# ATtiny_Connections.net
KiCad netlist of a schematic drawn in Altium Designer
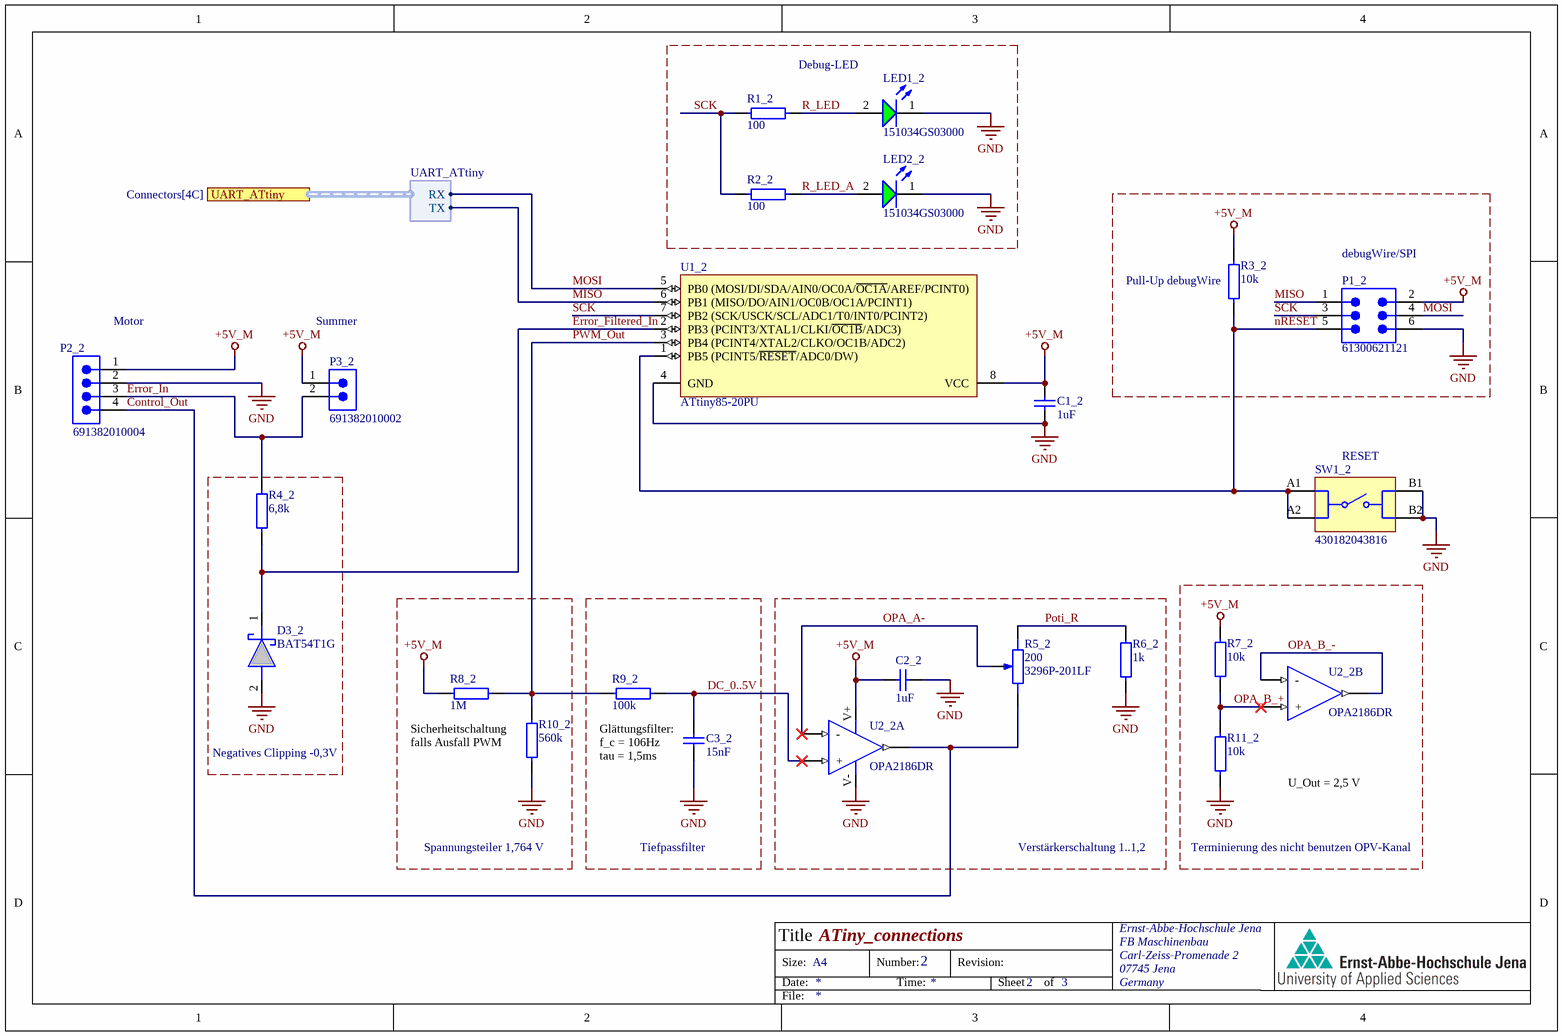
[diagram p0: ATtiny_Connections.SchDoc]

(export (version "E")
  (design (tool "Eeschema 10.0.6"))
  (components
    (comp (ref "C1_2")
      (value "1uF")
      (footprint "SMD-0805")
      (description "Kondensator")
      (libsource (lib "SMD") (part "C"))
    )
    (comp (ref "C2_2")
      (value "1uF")
      (footprint "SMD-0805")
      (description "Kondensator")
      (libsource (lib "SMD") (part "C"))
    )
    (comp (ref "C3_2")
      (value "15nF")
      (footprint "SMD-0805")
      (description "Kondensator")
      (libsource (lib "SMD") (part "C"))
    )
    (comp (ref "D3_2")
      (value "BAT54T1G")
      (footprint "SOD3716X135N")
      (fields (field (name "MOUSER PART NUMBER") "863-BAT54T1G"))
      (libsource (lib "BAT54T1G") (part "BAT54T1G"))
    )
    (comp (ref "LED1_2")
      (value "Green, 3.2V, 30°")
      (footprint "WL-TMRW_D3.9H5.3")
      (description "WL-TMRW Mono-color Round Waterclear, THT, D3.9 x H5.3mm, Green, 3.2V, 30°")
      (fields
        (field (name "MANUFACTURER PART NUMBER") "151034GS03000")
        (field (name "MANUFACTURER") "Wurth Elektronik")
      )
      (libsource (lib "WL-TMRW (rev22b)") (part "151034GS03000"))
    )
    (comp (ref "LED2_2")
      (value "Green, 3.2V, 30°")
      (footprint "WL-TMRW_D3.9H5.3")
      (description "WL-TMRW Mono-color Round Waterclear, THT, D3.9 x H5.3mm, Green, 3.2V, 30°")
      (fields
        (field (name "MANUFACTURER PART NUMBER") "151034GS03000")
        (field (name "MANUFACTURER") "Wurth Elektronik")
      )
      (libsource (lib "WL-TMRW (rev22b)") (part "151034GS03000"))
    )
    (comp (ref "P1_2")
      (value "61300621121")
      (footprint "61300621121")
      (description "WR-PHD Pin Header, THT, Vertical, pitch 2.54mm, 2 Row, 6P")
      (fields
        (field (name "MANUFACTURER PART NUMBER") "61300621121")
        (field (name "MANUFACTURER") "Wurth Elektronik")
      )
      (libsource (lib "Altium_WR-PHD (rev24a)") (part "61300621121"))
    )
    (comp (ref "P2_2")
      (value "691382010004")
      (footprint "691382010004")
      (description "WR-TBL Series 382 Horizontal PCB Header, THT, pitch 2.5mm, 04p")
      (fields (field (name "MANUFACTURER") "Wurth Elektronik"))
      (libsource (lib "Altium_WR-TBL_Pluggable Connector (rev25d)") (part "691382010004"))
    )
    (comp (ref "P3_2")
      (value "691382010002")
      (footprint "691382010002")
      (description "WR-TBL Series 382 Horizontal PCB Header, THT, pitch 2.5mm, 02p")
      (fields (field (name "MANUFACTURER") "Wurth Elektronik"))
      (libsource (lib "Altium_WR-TBL_Pluggable Connector (rev25d)") (part "691382010002"))
    )
    (comp (ref "R1_2")
      (value "100")
      (footprint "R-SMD-0805")
      (description "Widerstand")
      (libsource (lib "SMD") (part "R"))
    )
    (comp (ref "R2_2")
      (value "100")
      (footprint "R-SMD-0805")
      (description "Widerstand")
      (libsource (lib "SMD") (part "R"))
    )
    (comp (ref "R3_2")
      (value "10k")
      (footprint "R-SMD-0805")
      (description "Widerstand")
      (libsource (lib "SMD") (part "R"))
    )
    (comp (ref "R4_2")
      (value "6,8k")
      (footprint "R-SMD-0805")
      (description "Widerstand")
      (libsource (lib "SMD") (part "R"))
    )
    (comp (ref "R5_2")
      (value "200")
      (footprint "3296P-1-201LF")
      (fields
        (field (name "PARTNUMBER") "PV36P???C01B00")
        (field (name "MANUFACTURER PART NR.") "3296P-201LF")
      )
      (libsource (lib "TrimmPotentiometer") (part "3296P-1-201LF"))
    )
    (comp (ref "R6_2")
      (value "1k")
      (footprint "R-SMD-0805")
      (description "Widerstand")
      (libsource (lib "SMD") (part "R"))
    )
    (comp (ref "R7_2")
      (value "10k")
      (footprint "R-SMD-0805")
      (description "Widerstand")
      (libsource (lib "SMD") (part "R"))
    )
    (comp (ref "R8_2")
      (value "1M")
      (footprint "R-SMD-0805")
      (description "Widerstand")
      (libsource (lib "SMD") (part "R"))
    )
    (comp (ref "R9_2")
      (value "100k")
      (footprint "R-SMD-0805")
      (description "Widerstand")
      (libsource (lib "SMD") (part "R"))
    )
    (comp (ref "R10_2")
      (value "560k")
      (footprint "R-SMD-0805")
      (description "Widerstand")
      (libsource (lib "SMD") (part "R"))
    )
    (comp (ref "R11_2")
      (value "10k")
      (footprint "R-SMD-0805")
      (description "Widerstand")
      (libsource (lib "SMD") (part "R"))
    )
    (comp (ref "SW1_2")
      (value "430182043816")
      (footprint "430182043816")
      (description "WS-TASV SMT Tact Switch, 6mm x 6mm, 160gf, SPST-NO, 12V, 50mA")
      (fields (field (name "MANUFACTURER") "Wurth Elektronik"))
      (libsource (lib "Altium_WS-TASV (rev24d)") (part "430182043816"))
    )
    (comp (ref "U1_2")
      (value "ATtiny85-20PU")
      (footprint "8P3")
      (libsource (lib "Atmel Microcontroller tinyAVR") (part "ATtiny85-20PU"))
    )
    (comp (ref "U2_2")
      (value "OPA2186DR")
      (footprint "SOIC127P600-8BM")
      (libsource (lib "TI-OPV-BB") (part "OPA2186"))
    )
  )
  (nets
    (net (code "2") (name "+5V_M") (class "Default")
      (node (ref "C1_2") (pin "2") (pinfunction "2_2") (pintype "passive"))
      (node (ref "C2_2") (pin "2") (pinfunction "2_2") (pintype "passive"))
      (node (ref "P1_2") (pin "2") (pinfunction "2_2") (pintype "passive"))
      (node (ref "P2_2") (pin "1") (pinfunction "1_1") (pintype "passive"))
      (node (ref "P3_2") (pin "1") (pinfunction "1_1") (pintype "passive"))
      (node (ref "R3_2") (pin "2") (pinfunction "2_2") (pintype "passive"))
      (node (ref "R7_2") (pin "2") (pinfunction "2_2") (pintype "passive"))
      (node (ref "R8_2") (pin "1") (pinfunction "1_1") (pintype "passive"))
      (node (ref "U1_2") (pin "8") (pinfunction "VCC_8") (pintype "power_in"))
      (node (ref "U2_2") (pin "V+") (pinfunction "V+_V+") (pintype "power_in"))
    )
    (net (code "3") (name "/Control_Out") (class "Default")
      (node (ref "P2_2") (pin "4") (pinfunction "4_4") (pintype "passive"))
      (node (ref "R5_2") (pin "1") (pinfunction "1_1") (pintype "passive"))
      (node (ref "U2_2") (pin "OUTA") (pinfunction "OUT_OUTA") (pintype "output"))
    )
    (net (code "4") (name "/DC_0..5V") (class "Default")
      (node (ref "C3_2") (pin "2") (pinfunction "2_2") (pintype "passive"))
      (node (ref "R9_2") (pin "2") (pinfunction "2_2") (pintype "passive"))
      (node (ref "U2_2") (pin "IPA") (pinfunction "+_IPA") (pintype "input"))
    )
    (net (code "5") (name "/Error_Filtered_In") (class "Default")
      (node (ref "D3_2") (pin "1") (pinfunction "K_1") (pintype "passive"))
      (node (ref "R4_2") (pin "1") (pinfunction "1_1") (pintype "passive"))
      (node (ref "U1_2") (pin "2") (pinfunction "PB3_(PCINT3/XTAL1/CLKI/~{OC1B}/ADC3)_2") (pintype "bidirectional"))
    )
    (net (code "6") (name "/Error_In") (class "Default")
      (node (ref "P2_2") (pin "3") (pinfunction "3_3") (pintype "passive"))
      (node (ref "P3_2") (pin "2") (pinfunction "2_2") (pintype "passive"))
      (node (ref "R4_2") (pin "2") (pinfunction "2_2") (pintype "passive"))
    )
    (net (code "7") (name "/MISO") (class "Default")
      (node (ref "P1_2") (pin "1") (pinfunction "1_1") (pintype "passive"))
      (node (ref "U1_2") (pin "6") (pinfunction "PB1_(MISO/DO/AIN1/OC0B/OC1A/PCINT1)_6") (pintype "bidirectional"))
    )
    (net (code "8") (name "/MOSI") (class "Default")
      (node (ref "P1_2") (pin "4") (pinfunction "4_4") (pintype "passive"))
      (node (ref "U1_2") (pin "5") (pinfunction "PB0_(MOSI/DI/SDA/AIN0/OC0A/~{OC1A}/AREF/PCINT0)_5") (pintype "bidirectional"))
    )
    (net (code "9") (name "/OPA_A-") (class "Default")
      (node (ref "R5_2") (pin "2") (pinfunction "TAP_2") (pintype "passive"))
      (node (ref "U2_2") (pin "INA") (pinfunction "-_INA") (pintype "input"))
    )
    (net (code "10") (name "/OPA_B_+") (class "Default")
      (node (ref "R11_2") (pin "2") (pinfunction "2_2") (pintype "passive"))
      (node (ref "R7_2") (pin "1") (pinfunction "1_1") (pintype "passive"))
      (node (ref "U2_2") (pin "IPB") (pinfunction "+_IPB") (pintype "input"))
    )
    (net (code "11") (name "/OPA_B_-") (class "Default")
      (node (ref "U2_2") (pin "INB") (pinfunction "-_INB") (pintype "input"))
      (node (ref "U2_2") (pin "OUTB") (pinfunction "OUT_OUTB") (pintype "output"))
    )
    (net (code "12") (name "/PWM_Out") (class "Default")
      (node (ref "R10_2") (pin "2") (pinfunction "2_2") (pintype "passive"))
      (node (ref "R8_2") (pin "2") (pinfunction "2_2") (pintype "passive"))
      (node (ref "R9_2") (pin "1") (pinfunction "1_1") (pintype "passive"))
      (node (ref "U1_2") (pin "3") (pinfunction "PB4_(PCINT4/XTAL2/CLKO/OC1B/ADC2)_3") (pintype "bidirectional"))
    )
    (net (code "13") (name "/Poti_R") (class "Default")
      (node (ref "R5_2") (pin "3") (pinfunction "3_3") (pintype "passive"))
      (node (ref "R6_2") (pin "1") (pinfunction "1_1") (pintype "passive"))
    )
    (net (code "14") (name "/R_LED") (class "Default")
      (node (ref "LED1_2") (pin "2") (pinfunction "A_2") (pintype "passive"))
      (node (ref "R1_2") (pin "2") (pinfunction "2_2") (pintype "passive"))
    )
    (net (code "15") (name "/R_LED_A") (class "Default")
      (node (ref "LED2_2") (pin "2") (pinfunction "A_2") (pintype "passive"))
      (node (ref "R2_2") (pin "2") (pinfunction "2_2") (pintype "passive"))
    )
    (net (code "16") (name "/SCK") (class "Default")
      (node (ref "P1_2") (pin "3") (pinfunction "3_3") (pintype "passive"))
      (node (ref "R1_2") (pin "1") (pinfunction "1_1") (pintype "passive"))
      (node (ref "R2_2") (pin "1") (pinfunction "1_1") (pintype "passive"))
      (node (ref "U1_2") (pin "7") (pinfunction "PB2_(SCK/USCK/SCL/ADC1/T0/INT0/PCINT2)_7") (pintype "bidirectional"))
    )
    (net (code "17") (name "/nRESET") (class "Default")
      (node (ref "P1_2") (pin "5") (pinfunction "5_5") (pintype "passive"))
      (node (ref "R3_2") (pin "1") (pinfunction "1_1") (pintype "passive"))
      (node (ref "SW1_2") (pin "A1") (pinfunction "A1_A1") (pintype "passive"))
      (node (ref "SW1_2") (pin "A2") (pinfunction "A2_A2") (pintype "passive"))
      (node (ref "U1_2") (pin "1") (pinfunction "PB5_(PCINT5/~{RESET}/ADC0/DW)_1") (pintype "bidirectional"))
    )
    (net (code "19") (name "GND") (class "Default")
      (node (ref "C1_2") (pin "1") (pinfunction "1_1") (pintype "passive"))
      (node (ref "C2_2") (pin "1") (pinfunction "1_1") (pintype "passive"))
      (node (ref "C3_2") (pin "1") (pinfunction "1_1") (pintype "passive"))
      (node (ref "D3_2") (pin "2") (pinfunction "A_2") (pintype "passive"))
      (node (ref "LED1_2") (pin "1") (pinfunction "K_1") (pintype "passive"))
      (node (ref "LED2_2") (pin "1") (pinfunction "K_1") (pintype "passive"))
      (node (ref "P1_2") (pin "6") (pinfunction "6_6") (pintype "passive"))
      (node (ref "P2_2") (pin "2") (pinfunction "2_2") (pintype "passive"))
      (node (ref "R10_2") (pin "1") (pinfunction "1_1") (pintype "passive"))
      (node (ref "R11_2") (pin "1") (pinfunction "1_1") (pintype "passive"))
      (node (ref "R6_2") (pin "2") (pinfunction "2_2") (pintype "passive"))
      (node (ref "SW1_2") (pin "B1") (pinfunction "B1_B1") (pintype "passive"))
      (node (ref "SW1_2") (pin "B2") (pinfunction "B2_B2") (pintype "passive"))
      (node (ref "U1_2") (pin "4") (pinfunction "GND_4") (pintype "power_in"))
      (node (ref "U2_2") (pin "V-") (pinfunction "V-_V-") (pintype "power_in"))
    )
  )
)
